# StartStopSwitch_Ver3_0.net
KiCad netlist of a schematic drawn in EAGLE
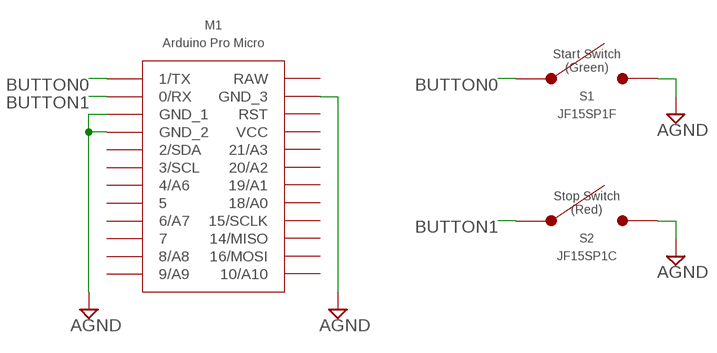
[diagram p0: schematic, sheet 1]

(export (version "E")
  (design (tool "Eeschema 10.0.6"))
  (components
    (comp (ref "M1")
      (value "PRO_MICRO_SMD")
      (footprint "eagle-import:PRO_MICRO_SMD")
      (libsource (lib "eagle-import") (part "PRO_MICRO_SMD"))
    )
    (comp (ref "S1")
      (value "JF15SP1F")
      (footprint "eagle-import:JF15SP1")
      (libsource (lib "eagle-import") (part "JF15SP1F"))
    )
    (comp (ref "S2")
      (value "JF15SP1C")
      (footprint "eagle-import:JF15SP1")
      (libsource (lib "eagle-import") (part "JF15SP1C"))
    )
  )
  (nets
    (net (code "1") (name "/BUTTON0") (class "Default")
      (node (ref "M1") (pin "1") (pinfunction "1/TX_1") (pintype "bidirectional"))
      (node (ref "S1") (pin "1") (pinfunction "P$1_1") (pintype "bidirectional"))
      (node (ref "S1") (pin "2") (pinfunction "P$1_2") (pintype "bidirectional"))
    )
    (net (code "2") (name "/BUTTON1") (class "Default")
      (node (ref "M1") (pin "2") (pinfunction "0/RX_2") (pintype "bidirectional"))
      (node (ref "S2") (pin "1") (pinfunction "P$1_1") (pintype "bidirectional"))
      (node (ref "S2") (pin "2") (pinfunction "P$1_2") (pintype "bidirectional"))
    )
    (net (code "3") (name "AGND") (class "Default")
      (node (ref "M1") (pin "23") (pinfunction "GND_3_23") (pintype "bidirectional"))
      (node (ref "M1") (pin "3") (pinfunction "GND_1_3") (pintype "bidirectional"))
      (node (ref "M1") (pin "4") (pinfunction "GND_2_4") (pintype "bidirectional"))
      (node (ref "S1") (pin "3") (pinfunction "P$2_3") (pintype "bidirectional"))
      (node (ref "S1") (pin "4") (pinfunction "P$2_4") (pintype "bidirectional"))
      (node (ref "S2") (pin "3") (pinfunction "P$2_3") (pintype "bidirectional"))
      (node (ref "S2") (pin "4") (pinfunction "P$2_4") (pintype "bidirectional"))
    )
    (net (code "4") (name "unconnected-(M1-2{slash}SDA-Pad5)") (class "Default")
      (node (ref "M1") (pin "5") (pinfunction "2/SDA_5") (pintype "bidirectional"))
    )
    (net (code "5") (name "unconnected-(M1-3{slash}SCL-Pad6)") (class "Default")
      (node (ref "M1") (pin "6") (pinfunction "3/SCL_6") (pintype "bidirectional"))
    )
    (net (code "6") (name "unconnected-(M1-4{slash}A6-Pad7)") (class "Default")
      (node (ref "M1") (pin "7") (pinfunction "4/A6_7") (pintype "bidirectional"))
    )
    (net (code "7") (name "unconnected-(M1-5-Pad8)") (class "Default")
      (node (ref "M1") (pin "8") (pinfunction "5_8") (pintype "bidirectional"))
    )
    (net (code "8") (name "unconnected-(M1-6{slash}A7-Pad9)") (class "Default")
      (node (ref "M1") (pin "9") (pinfunction "6/A7_9") (pintype "bidirectional"))
    )
    (net (code "9") (name "unconnected-(M1-7-Pad10)") (class "Default")
      (node (ref "M1") (pin "10") (pinfunction "7_10") (pintype "bidirectional"))
    )
    (net (code "10") (name "unconnected-(M1-8{slash}A8-Pad11)") (class "Default")
      (node (ref "M1") (pin "11") (pinfunction "8/A8_11") (pintype "bidirectional"))
    )
    (net (code "11") (name "unconnected-(M1-9{slash}A9-Pad12)") (class "Default")
      (node (ref "M1") (pin "12") (pinfunction "9/A9_12") (pintype "bidirectional"))
    )
    (net (code "12") (name "unconnected-(M1-10{slash}A10-Pad13)") (class "Default")
      (node (ref "M1") (pin "13") (pinfunction "10/A10_13") (pintype "bidirectional"))
    )
    (net (code "13") (name "unconnected-(M1-14{slash}MISO-Pad15)") (class "Default")
      (node (ref "M1") (pin "15") (pinfunction "14/MISO_15") (pintype "bidirectional"))
    )
    (net (code "14") (name "unconnected-(M1-15{slash}SCLK-Pad16)") (class "Default")
      (node (ref "M1") (pin "16") (pinfunction "15/SCLK_16") (pintype "bidirectional"))
    )
    (net (code "15") (name "unconnected-(M1-16{slash}MOSI-Pad14)") (class "Default")
      (node (ref "M1") (pin "14") (pinfunction "16/MOSI_14") (pintype "bidirectional"))
    )
    (net (code "16") (name "unconnected-(M1-18{slash}A0-Pad17)") (class "Default")
      (node (ref "M1") (pin "17") (pinfunction "18/A0_17") (pintype "bidirectional"))
    )
    (net (code "17") (name "unconnected-(M1-19{slash}A1-Pad18)") (class "Default")
      (node (ref "M1") (pin "18") (pinfunction "19/A1_18") (pintype "bidirectional"))
    )
    (net (code "18") (name "unconnected-(M1-20{slash}A2-Pad19)") (class "Default")
      (node (ref "M1") (pin "19") (pinfunction "20/A2_19") (pintype "bidirectional"))
    )
    (net (code "19") (name "unconnected-(M1-21{slash}A3-Pad20)") (class "Default")
      (node (ref "M1") (pin "20") (pinfunction "21/A3_20") (pintype "bidirectional"))
    )
    (net (code "20") (name "unconnected-(M1-RAW-Pad24)") (class "Default")
      (node (ref "M1") (pin "24") (pinfunction "RAW_24") (pintype "bidirectional"))
    )
    (net (code "21") (name "unconnected-(M1-RST-Pad22)") (class "Default")
      (node (ref "M1") (pin "22") (pinfunction "RST_22") (pintype "bidirectional"))
    )
    (net (code "22") (name "unconnected-(M1-VCC-Pad21)") (class "Default")
      (node (ref "M1") (pin "21") (pinfunction "VCC_21") (pintype "bidirectional"))
    )
  )
)
